# FeedbackLoop.net
KiCad netlist of a schematic drawn in Altium Designer
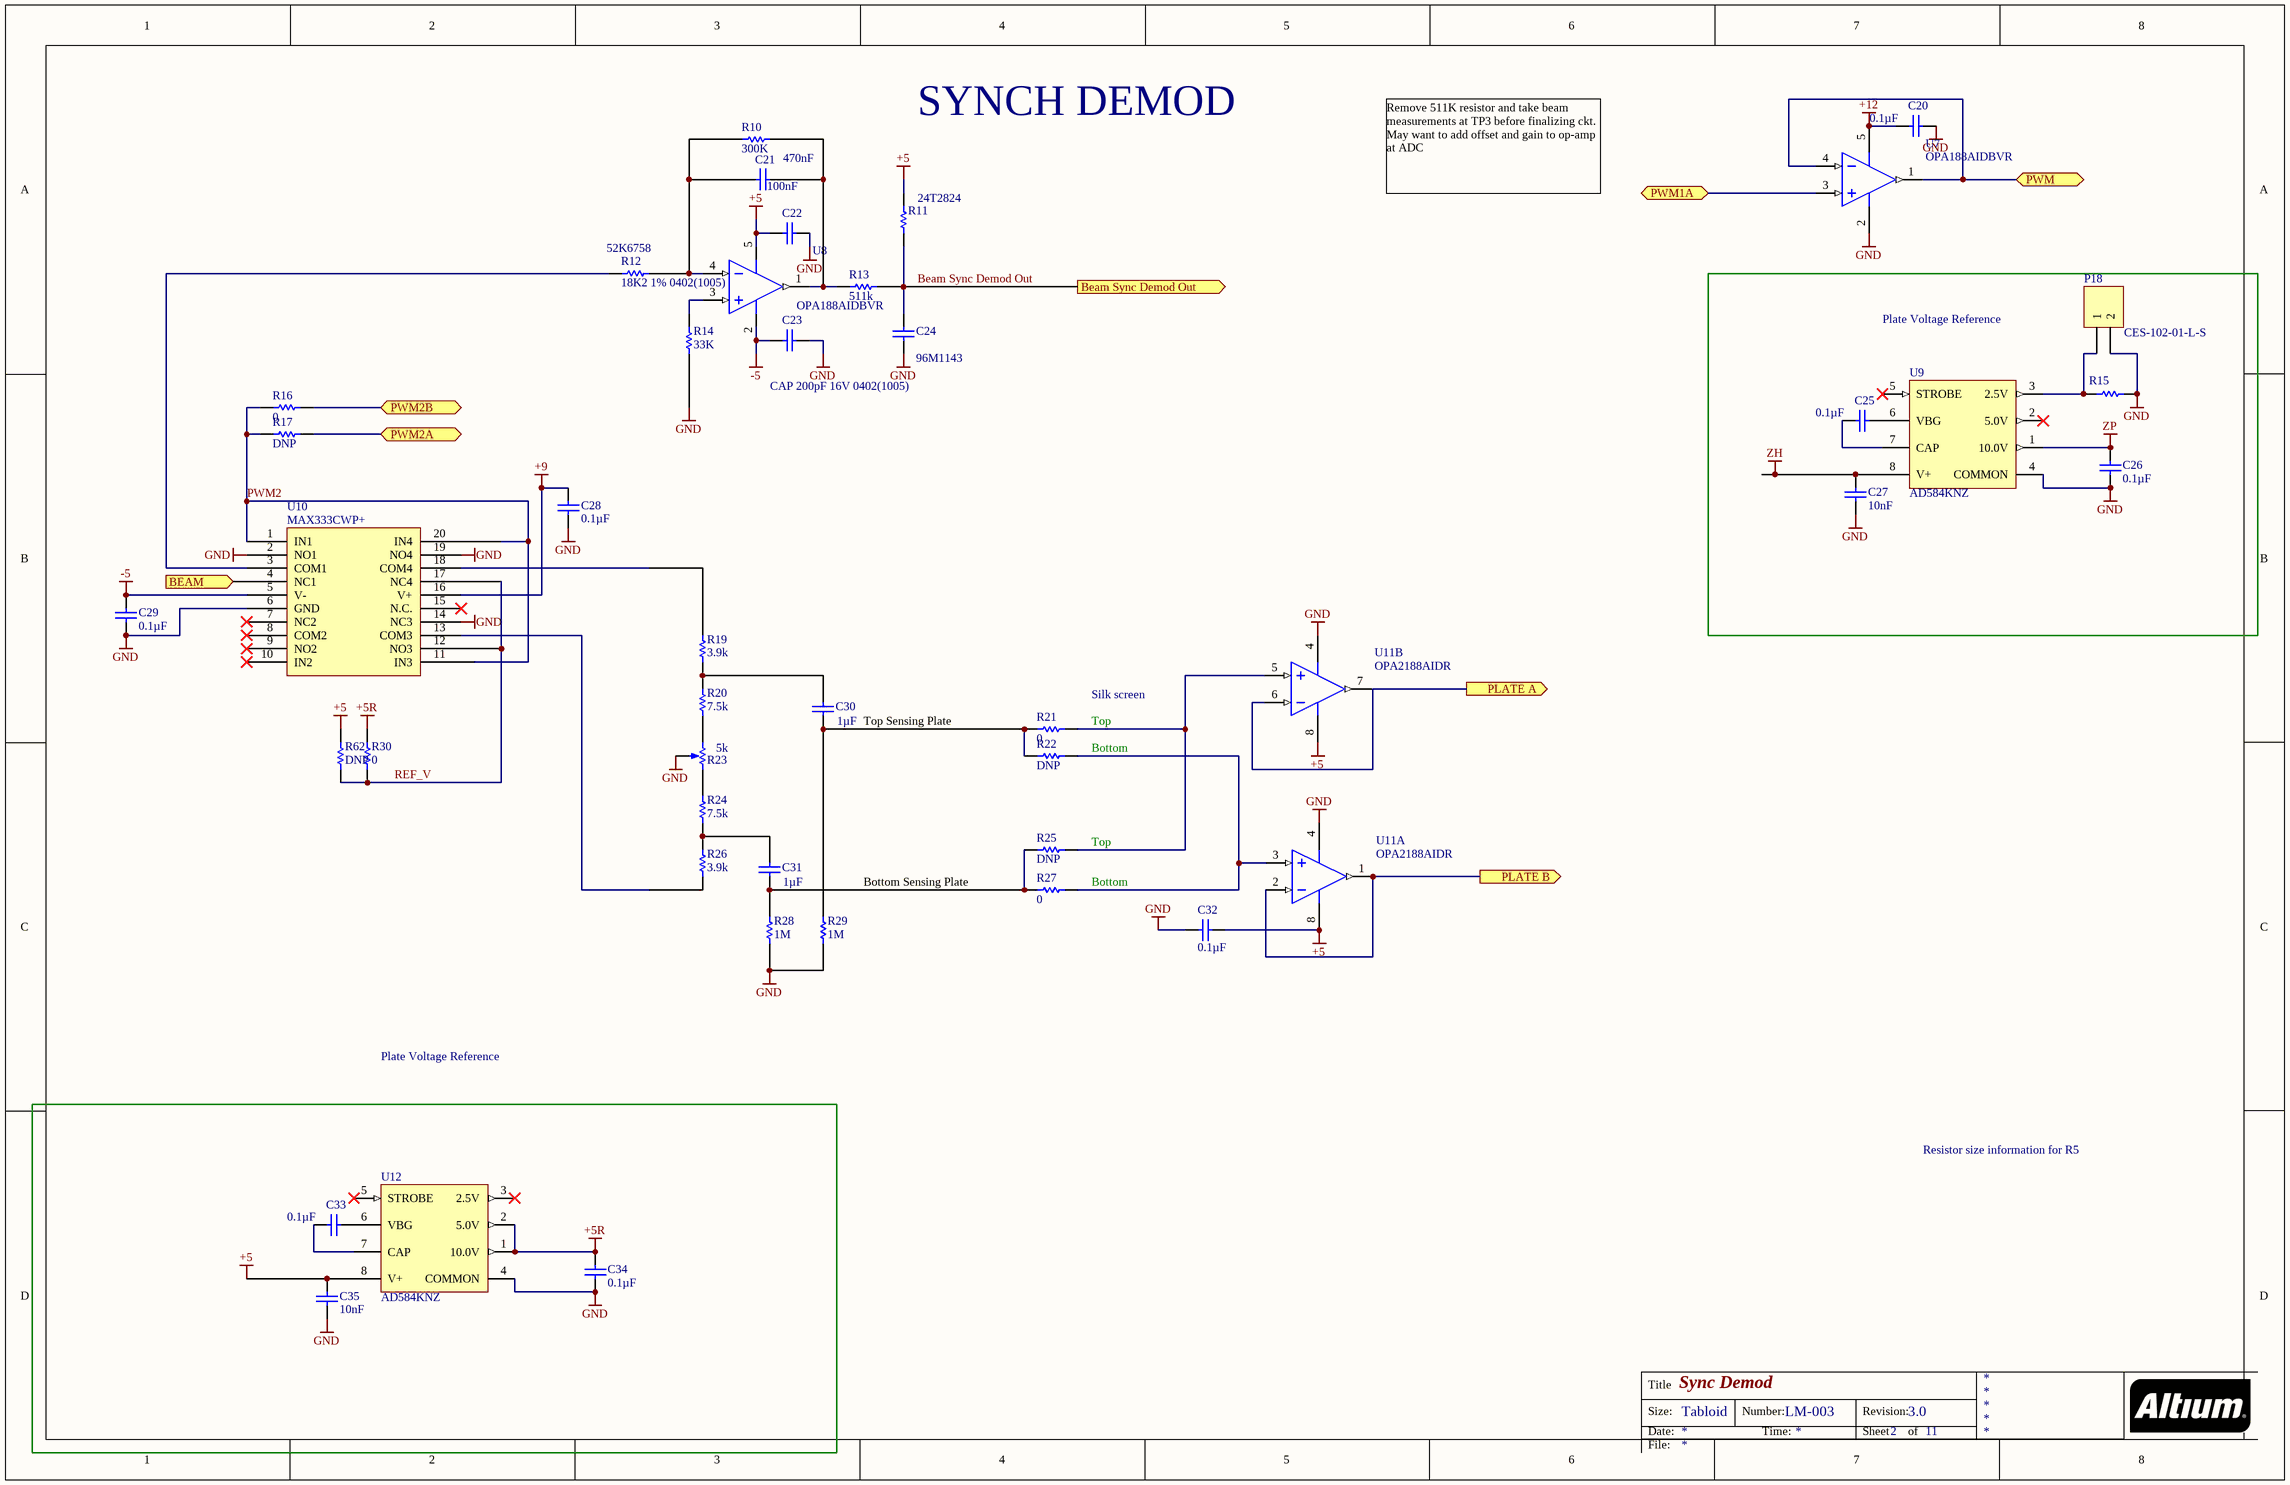
[diagram p0: FeedbackLoop.SchDoc]

(export (version "E")
  (design (tool "Eeschema 10.0.6"))
  (components
    (comp (ref "C20")
      (value "CAP 100nF 25V 0805(2012)")
      (footprint "CAPC0805(2012)100_N")
      (description "CAP 100nF 25V -20% to +80% 0805 (2012 Metric) Thickness 1mm SMD")
      (fields
        (field (name "MANUFACTURER") "Murata Electronics North America")
        (field (name "MANUFACTURER PART NUMBER") "GRM21BR71E104KA01L")
        (field (name "CAPACITANCE") "0.1µF")
      )
      (libsource (lib "Altium Content Vault") (part "CMP-1036-04416-1"))
    )
    (comp (ref "C21")
      (value "~")
      (footprint "CAPC0402(1005)60_L")
      (fields
        (field (name "MANUFACTURER") "TDK")
        (field (name "MANUFACTURER PART NUMBER") "C1005X5R1E474M050BB")
        (field (name "TOLERANCE") "20%")
        (field (name "CAPACITANCE") "470nF")
      )
      (libsource (lib "Altium Content Vault") (part "CMP-1034-01343-1"))
    )
    (comp (ref "C22")
      (value "~")
      (footprint "CAPC0402(1005)60_L")
      (fields
        (field (name "MANUFACTURER") "Kemet")
        (field (name "MANUFACTURER PART NUMBER") "C0402C104K4RACAUTO")
        (field (name "CAPACITANCE") "100nF")
        (field (name "TOLERANCE") "10%")
      )
      (libsource (lib "Altium Content Vault") (part "CMP-1034-01343-1"))
    )
    (comp (ref "C23")
      (value "CAP 200pF 16V 0402(1005)")
      (footprint "CAPC0402(1005)60_L")
      (description "CAP 200pF 16V ±2% 0402 (1005 Metric) Thickness 0.6mm SMD")
      (fields (field (name "TOLERANCE") "Â±2%") (field (name "MANUFACTURER") "Kemet"))
      (libsource (lib "Altium Content Vault") (part "CMP-1034-01343-1"))
    )
    (comp (ref "C24")
      (value "~")
      (footprint "CAPC0402(1005)60_L")
      (fields
        (field (name "SUPPLIER PART NUMBER 1") "96M1143")
        (field (name "MANUFACTURER") "AVX")
        (field (name "MANUFACTURER PART NUMBER") "04025A220JAT2A")
      )
      (libsource (lib "Altium Content Vault") (part "CMP-1034-01343-1"))
    )
    (comp (ref "C25")
      (value "CAP 100nF 25V 0805(2012)")
      (footprint "CAPC0805(2012)100_N")
      (description "CAP 100nF 25V -20% to +80% 0805 (2012 Metric) Thickness 1mm SMD")
      (fields
        (field (name "MANUFACTURER") "Murata Electronics North America")
        (field (name "MANUFACTURER PART NUMBER") "GRM21BR71E104KA01L")
        (field (name "CAPACITANCE") "0.1µF")
      )
      (libsource (lib "Altium Content Vault") (part "CMP-1036-04416-1"))
    )
    (comp (ref "C26")
      (value "CAP CER 0.1UF 25V X7R 0805")
      (footprint "CAPC0805(2012)145_N")
      (fields
        (field (name "MANUFACTURER") "Murata Electronics North America")
        (field (name "MANUFACTURER PART NUMBER") "GRM21BR71E104KA01L")
        (field (name "CAPACITANCE") "0.1µF")
        (field (name "TOLERANCE") "±10%")
      )
      (libsource (lib "Altium Content Vault") (part "CMP-1036-04795-1"))
    )
    (comp (ref "C27")
      (value "Multilayer Ceramic Capacitors MLCC - SMD/SMT 0.01uF 50volts 10% X7R")
      (footprint "CAPC0805(2012)145_N")
      (fields
        (field (name "MANUFACTURER") "Kemet")
        (field (name "MANUFACTURER PART NUMBER") "C0805C103K5RACAUTO")
        (field (name "CAPACITANCE") "10nF")
        (field (name "TOLERANCE") "10%")
      )
      (libsource (lib "Altium Content Vault") (part "CMP-1036-04795-1"))
    )
    (comp (ref "C28")
      (value "CAP CER 0.1UF 25V X7R 0805")
      (footprint "CAPC0805(2012)145_N")
      (fields
        (field (name "MANUFACTURER") "Murata Electronics North America")
        (field (name "MANUFACTURER PART NUMBER") "GRM21BR71E104KA01L")
        (field (name "CAPACITANCE") "0.1µF")
        (field (name "TOLERANCE") "±10%")
      )
      (libsource (lib "Altium Content Vault") (part "CMP-1036-04795-1"))
    )
    (comp (ref "C29")
      (value "CAP CER 0.1UF 25V X7R 0805")
      (footprint "CAPC0805(2012)145_N")
      (fields
        (field (name "MANUFACTURER") "Murata Electronics North America")
        (field (name "MANUFACTURER PART NUMBER") "GRM21BR71E104KA01L")
        (field (name "CAPACITANCE") "0.1µF")
        (field (name "TOLERANCE") "±10%")
      )
      (libsource (lib "Altium Content Vault") (part "CMP-1036-04795-1"))
    )
    (comp (ref "C30")
      (value "CAP CER 1UF 25V X7R 0805")
      (footprint "CAPC0805(2012)155_L")
      (fields
        (field (name "MANUFACTURER") "Murata Electronics North America")
        (field (name "MANUFACTURER PART NUMBER") "GRM21BR71E105KA99L")
        (field (name "CAPACITANCE") "1µF")
        (field (name "TOLERANCE") "±10%")
      )
      (libsource (lib "Altium Content Vault") (part "CMP-1036-04882-1"))
    )
    (comp (ref "C31")
      (value "CAP CER 1UF 25V X7R 0805")
      (footprint "CAPC0805(2012)155_L")
      (fields
        (field (name "MANUFACTURER") "Murata Electronics North America")
        (field (name "MANUFACTURER PART NUMBER") "GRM21BR71E105KA99L")
        (field (name "CAPACITANCE") "1µF")
        (field (name "TOLERANCE") "±10%")
      )
      (libsource (lib "Altium Content Vault") (part "CMP-1036-04882-1"))
    )
    (comp (ref "C32")
      (value "CAP CER 0.1UF 25V X7R 0805")
      (footprint "CAPC0805(2012)155_L")
      (fields
        (field (name "MANUFACTURER") "Murata Electronics North America")
        (field (name "MANUFACTURER PART NUMBER") "GRM21BR71E104KA01L")
        (field (name "CAPACITANCE") "0.1µF")
        (field (name "TOLERANCE") "±10%")
      )
      (libsource (lib "Altium Content Vault") (part "CMP-1036-04882-1"))
    )
    (comp (ref "C33")
      (value "CAP 100nF 25V 0805(2012)")
      (footprint "CAPC0805(2012)100_N")
      (description "CAP 100nF 25V -20% to +80% 0805 (2012 Metric) Thickness 1mm SMD")
      (fields
        (field (name "MANUFACTURER") "Murata Electronics North America")
        (field (name "MANUFACTURER PART NUMBER") "GRM21BR71E104KA01L")
        (field (name "CAPACITANCE") "0.1µF")
      )
      (libsource (lib "Altium Content Vault") (part "CMP-1036-04416-1"))
    )
    (comp (ref "C34")
      (value "CAP CER 0.1UF 25V X7R 0805")
      (footprint "CAPC0805(2012)145_N")
      (fields
        (field (name "MANUFACTURER") "Murata Electronics North America")
        (field (name "MANUFACTURER PART NUMBER") "GRM21BR71E104KA01L")
        (field (name "CAPACITANCE") "0.1µF")
        (field (name "TOLERANCE") "±10%")
      )
      (libsource (lib "Altium Content Vault") (part "CMP-1036-04795-1"))
    )
    (comp (ref "C35")
      (value "Multilayer Ceramic Capacitors MLCC - SMD/SMT 0.01uF 50volts 10% X7R")
      (footprint "CAPC0805(2012)145_N")
      (fields
        (field (name "MANUFACTURER") "Kemet")
        (field (name "MANUFACTURER PART NUMBER") "C0805C103K5RACAUTO")
        (field (name "CAPACITANCE") "10nF")
        (field (name "TOLERANCE") "10%")
      )
      (libsource (lib "Altium Content Vault") (part "CMP-1036-04795-1"))
    )
    (comp (ref "P18")
      (value "LOW PROFILE .025\" SQUARE STRIPS")
      (footprint "CES-102-01-L-S")
      (fields
        (field (name "MANUFACTURER") "Samtec Inc.")
        (field (name "MANUFACTURER PART NUMBER") "CES-102-01-L-S")
      )
      (libsource (lib "Miscellaneous Connectors") (part "Header 2"))
    )
    (comp (ref "R10")
      (value "300K")
      (footprint "RESC0402(1005)_M")
      (libsource (lib "Altium Content Vault") (part "CMP-1011-00651-1"))
    )
    (comp (ref "R11")
      (value "~")
      (footprint "RESC0402(1005)_M")
      (fields
        (field (name "SUPPLIER PART NUMBER 1") "24T2824")
        (field (name "MANUFACTURER") "VISHAY")
        (field (name "MANUFACTURER PART NUMBER") "CRCW0402100KFKEDHP")
      )
      (libsource (lib "Altium Content Vault") (part "CMP-1011-00651-1"))
    )
    (comp (ref "R12")
      (value "18K2 1% 0402(1005)")
      (footprint "RESC0402(1005)_M")
      (description "18K2 0.063W 1% 0402 (1005 Metric)  SMD")
      (fields
        (field (name "SUPPLIER PART NUMBER 1") "52K6758")
        (field (name "MANUFACTURER") "VISHAY")
        (field (name "MANUFACTURER PART NUMBER") "CRCW040218K2FKED")
      )
      (libsource (lib "Altium Content Vault") (part "CMP-1011-00651-1"))
    )
    (comp (ref "R13")
      (value "511k")
      (footprint "RESC0402(1005)_M")
      (libsource (lib "Altium Content Vault") (part "CMP-1011-00651-1"))
    )
    (comp (ref "R14")
      (value "33K")
      (footprint "RESC0402(1005)_M")
      (libsource (lib "Altium Content Vault") (part "CMP-1011-00651-1"))
    )
    (comp (ref "R15")
      (value "TBD")
      (footprint "VH102K")
      (libsource (lib "altium-import") (part "root_0_CMP-1013-00393-1_"))
    )
    (comp (ref "R16")
      (value "0")
      (footprint "RESC0402(1005)_M")
      (libsource (lib "Altium Content Vault") (part "CMP-1011-00651-1"))
    )
    (comp (ref "R17")
      (value "DNP")
      (footprint "RESC0402(1005)_M")
      (libsource (lib "Altium Content Vault") (part "CMP-1011-00651-1"))
    )
    (comp (ref "R19")
      (value "3.9k")
      (footprint "RESC0402(1005)_M")
      (libsource (lib "Altium Content Vault") (part "CMP-1011-00651-1"))
    )
    (comp (ref "R20")
      (value "7.5k")
      (footprint "RESC0402(1005)_M")
      (libsource (lib "Altium Content Vault") (part "CMP-1011-00651-1"))
    )
    (comp (ref "R21")
      (value "0")
      (footprint "RESC0402(1005)_M")
      (libsource (lib "Altium Content Vault") (part "CMP-1011-00651-1"))
    )
    (comp (ref "R22")
      (value "DNP")
      (footprint "RESC0402(1005)_M")
      (libsource (lib "Altium Content Vault") (part "CMP-1011-00651-1"))
    )
    (comp (ref "R23")
      (value "TRIMMER 5K OHM 0.25W PC PIN")
      (footprint "Trimmer 2.54")
      (fields
        (field (name "MANUFACTURER") "Vishay Foil Resistors (Division of Vishay Precision Group)")
        (field (name "MANUFACTURER PART NUMBER") "Y00535K00000J0L")
        (field (name "RESISTANCE (OHMS)") "5k")
        (field (name "TOLERANCE") "±5%")
      )
      (libsource (lib "ZLS_Schematic_lib") (part "Trimmer"))
    )
    (comp (ref "R24")
      (value "7.5k")
      (footprint "RESC0402(1005)_M")
      (libsource (lib "Altium Content Vault") (part "CMP-1011-00651-1"))
    )
    (comp (ref "R25")
      (value "DNP")
      (footprint "RESC0402(1005)_M")
      (libsource (lib "Altium Content Vault") (part "CMP-1011-00651-1"))
    )
    (comp (ref "R26")
      (value "3.9k")
      (footprint "RESC0402(1005)_M")
      (libsource (lib "Altium Content Vault") (part "CMP-1011-00651-1"))
    )
    (comp (ref "R27")
      (value "0")
      (footprint "RESC0402(1005)_M")
      (libsource (lib "Altium Content Vault") (part "CMP-1011-00651-1"))
    )
    (comp (ref "R28")
      (value "1M")
      (footprint "RESC0402(1005)_M")
      (libsource (lib "Altium Content Vault") (part "CMP-1011-00651-1"))
    )
    (comp (ref "R29")
      (value "1M")
      (footprint "RESC0402(1005)_M")
      (libsource (lib "Altium Content Vault") (part "CMP-1011-00651-1"))
    )
    (comp (ref "R30")
      (value "0")
      (footprint "RESC0402(1005)_M")
      (libsource (lib "Altium Content Vault") (part "CMP-1011-00651-1"))
    )
    (comp (ref "R62")
      (value "DNP")
      (footprint "RESC0402(1005)_M")
      (libsource (lib "Altium Content Vault") (part "CMP-1011-00651-1"))
    )
    (comp (ref "U7")
      (value "OPA188AIDBVR")
      (footprint "DBV0005A_M")
      (fields (field (name "MANUFACTURER") "Texas Instruments"))
      (libsource (lib "Altium Content Vault") (part "CMP-0809-00005-2"))
    )
    (comp (ref "U8")
      (value "OPA188AIDBVR")
      (footprint "DBV0005A_M")
      (fields (field (name "MANUFACTURER") "Texas Instruments"))
      (libsource (lib "Altium Content Vault") (part "CMP-0809-00005-2"))
    )
    (comp (ref "U9")
      (value "AD584KNZ")
      (footprint "ADI-N-8")
      (fields (field (name "MANUFACTURER") "Analog Devices"))
      (libsource (lib "Altium Content Vault") (part "ADI-AD584-N-8"))
    )
    (comp (ref "U10")
      (value "MAX333CWP+")
      (footprint "TSOP65P640X90-20N")
      (description "IC SWITCH QUAD SPDT 20TSSOP")
      (fields (field (name "MANUFACTURER") "Maxim") (field (name "MANUFACTURER PART NUMBER") "MAX333AEUP+"))
      (libsource (lib "ZLS_Schematic_lib") (part "MAX333CWP+"))
    )
    (comp (ref "U11")
      (value "OPA2188AIDR")
      (footprint "D0008A_L")
      (fields (field (name "MANUFACTURER") "Texas Instruments"))
      (libsource (lib "Altium Content Vault") (part "CMP-0272-00241-3"))
    )
    (comp (ref "U12")
      (value "AD584KNZ")
      (footprint "ADI-N-8")
      (fields (field (name "MANUFACTURER") "Analog Devices"))
      (libsource (lib "Altium Content Vault") (part "ADI-AD584-N-8"))
    )
  )
  (nets
    (net (code "1") (name "+5") (class "Default")
      (node (ref "C22") (pin "1") (pinfunction "1_1") (pintype "passive"))
      (node (ref "C32") (pin "1") (pinfunction "1_1") (pintype "passive"))
      (node (ref "C35") (pin "1") (pinfunction "1_1") (pintype "passive"))
      (node (ref "R11") (pin "2") (pinfunction "2_2") (pintype "passive"))
      (node (ref "R62") (pin "2") (pinfunction "2_2") (pintype "passive"))
      (node (ref "U11") (pin "8") (pinfunction "V+_8") (pintype "power_in"))
      (node (ref "U12") (pin "8") (pinfunction "V+_8") (pintype "power_in"))
      (node (ref "U8") (pin "5") (pinfunction "V+_5") (pintype "power_in"))
    )
    (net (code "2") (name "+5R") (class "Default")
      (node (ref "C34") (pin "1") (pinfunction "1_1") (pintype "passive"))
      (node (ref "R30") (pin "2") (pinfunction "2_2") (pintype "passive"))
      (node (ref "U12") (pin "1") (pinfunction "10.0V_1") (pintype "output"))
      (node (ref "U12") (pin "2") (pinfunction "5.0V_2") (pintype "output"))
    )
    (net (code "3") (name "+9") (class "Default")
      (node (ref "C28") (pin "2") (pinfunction "2_2") (pintype "passive"))
      (node (ref "U10") (pin "16") (pinfunction "V+_16") (pintype "power_in"))
    )
    (net (code "4") (name "+12") (class "Default")
      (node (ref "C20") (pin "1") (pinfunction "1_1") (pintype "passive"))
      (node (ref "U7") (pin "5") (pinfunction "V+_5") (pintype "power_in"))
    )
    (net (code "5") (name "-5") (class "Default")
      (node (ref "C23") (pin "1") (pinfunction "1_1") (pintype "passive"))
      (node (ref "C29") (pin "1") (pinfunction "1_1") (pintype "passive"))
      (node (ref "U10") (pin "5") (pinfunction "V-_5") (pintype "power_in"))
      (node (ref "U8") (pin "2") (pinfunction "V-_2") (pintype "power_in"))
    )
    (net (code "6") (name "/BEAM") (class "Default")
      (node (ref "U10") (pin "4") (pinfunction "NC1_4") (pintype "passive"))
    )
    (net (code "7") (name "/Beam Sync Demod Out") (class "Default")
      (node (ref "C24") (pin "2") (pinfunction "2_2") (pintype "passive"))
      (node (ref "R11") (pin "1") (pinfunction "1_1") (pintype "passive"))
      (node (ref "R13") (pin "2") (pinfunction "2_2") (pintype "passive"))
    )
    (net (code "8") (name "/PLATE A") (class "Default")
      (node (ref "U11") (pin "6") (pinfunction "IN_B-_6") (pintype "input"))
    )
    (net (code "9") (name "/PLATE B") (class "Default")
      (node (ref "U11") (pin "1") (pinfunction "OUT_A_1") (pintype "output"))
      (node (ref "U11") (pin "2") (pinfunction "IN_A-_2") (pintype "input"))
    )
    (net (code "10") (name "/PWM") (class "Default")
      (node (ref "U7") (pin "1") (pinfunction "OUT_1") (pintype "output"))
      (node (ref "U7") (pin "4") (pinfunction "IN-_4") (pintype "input"))
    )
    (net (code "11") (name "/PWM1A") (class "Default")
      (node (ref "U7") (pin "3") (pinfunction "IN+_3") (pintype "input"))
    )
    (net (code "12") (name "/PWM2") (class "Default")
      (node (ref "R16") (pin "2") (pinfunction "2_2") (pintype "passive"))
      (node (ref "R17") (pin "2") (pinfunction "2_2") (pintype "passive"))
      (node (ref "U10") (pin "1") (pinfunction "IN1_1") (pintype "passive"))
      (node (ref "U10") (pin "11") (pinfunction "IN3_11") (pintype "passive"))
      (node (ref "U10") (pin "20") (pinfunction "IN4_20") (pintype "passive"))
    )
    (net (code "13") (name "/PWM2A") (class "Default")
      (node (ref "R17") (pin "1") (pinfunction "1_1") (pintype "passive"))
    )
    (net (code "14") (name "/PWM2B") (class "Default")
      (node (ref "R16") (pin "1") (pinfunction "1_1") (pintype "passive"))
    )
    (net (code "15") (name "/REF_V") (class "Default")
      (node (ref "R30") (pin "1") (pinfunction "1_1") (pintype "passive"))
      (node (ref "R62") (pin "1") (pinfunction "1_1") (pintype "passive"))
      (node (ref "U10") (pin "12") (pinfunction "NO3_12") (pintype "passive"))
      (node (ref "U10") (pin "17") (pinfunction "NC4_17") (pintype "passive"))
    )
    (net (code "16") (name "GND") (class "Default")
      (node (ref "C20") (pin "2") (pinfunction "2_2") (pintype "passive"))
      (node (ref "C22") (pin "2") (pinfunction "2_2") (pintype "passive"))
      (node (ref "C23") (pin "2") (pinfunction "2_2") (pintype "passive"))
      (node (ref "C24") (pin "1") (pinfunction "1_1") (pintype "passive"))
      (node (ref "C26") (pin "2") (pinfunction "2_2") (pintype "passive"))
      (node (ref "C27") (pin "2") (pinfunction "2_2") (pintype "passive"))
      (node (ref "C28") (pin "1") (pinfunction "1_1") (pintype "passive"))
      (node (ref "C29") (pin "2") (pinfunction "2_2") (pintype "passive"))
      (node (ref "C32") (pin "2") (pinfunction "2_2") (pintype "passive"))
      (node (ref "C34") (pin "2") (pinfunction "2_2") (pintype "passive"))
      (node (ref "C35") (pin "2") (pinfunction "2_2") (pintype "passive"))
      (node (ref "P18") (pin "2") (pinfunction "2_2") (pintype "passive"))
      (node (ref "R14") (pin "1") (pinfunction "1_1") (pintype "passive"))
      (node (ref "R15") (pin "2") (pinfunction "2_2") (pintype "passive"))
      (node (ref "R23") (pin "2") (pinfunction "b_2") (pintype "passive"))
      (node (ref "R28") (pin "1") (pinfunction "1_1") (pintype "passive"))
      (node (ref "R29") (pin "1") (pinfunction "1_1") (pintype "passive"))
      (node (ref "U10") (pin "14") (pinfunction "NC3_14") (pintype "passive"))
      (node (ref "U10") (pin "19") (pinfunction "NO4_19") (pintype "passive"))
      (node (ref "U10") (pin "2") (pinfunction "NO1_2") (pintype "passive"))
      (node (ref "U10") (pin "6") (pinfunction "GND_6") (pintype "passive"))
      (node (ref "U11") (pin "4") (pinfunction "V-_4") (pintype "power_in"))
      (node (ref "U12") (pin "4") (pinfunction "COMMON_4") (pintype "passive"))
      (node (ref "U7") (pin "2") (pinfunction "V-_2") (pintype "power_in"))
      (node (ref "U9") (pin "4") (pinfunction "COMMON_4") (pintype "passive"))
    )
    (net (code "17") (name "Net-(C30-Pad1)") (class "Default")
      (node (ref "C30") (pin "1") (pinfunction "1_1") (pintype "passive"))
      (node (ref "R21") (pin "2") (pinfunction "2_2") (pintype "passive"))
      (node (ref "R22") (pin "2") (pinfunction "2_2") (pintype "passive"))
      (node (ref "R29") (pin "2") (pinfunction "2_2") (pintype "passive"))
    )
    (net (code "18") (name "Net-(C30-Pad2)") (class "Default")
      (node (ref "C30") (pin "2") (pinfunction "2_2") (pintype "passive"))
      (node (ref "R19") (pin "1") (pinfunction "1_1") (pintype "passive"))
      (node (ref "R20") (pin "2") (pinfunction "2_2") (pintype "passive"))
    )
    (net (code "19") (name "Net-(C31-Pad1)") (class "Default")
      (node (ref "C31") (pin "1") (pinfunction "1_1") (pintype "passive"))
      (node (ref "R25") (pin "2") (pinfunction "2_2") (pintype "passive"))
      (node (ref "R27") (pin "2") (pinfunction "2_2") (pintype "passive"))
      (node (ref "R28") (pin "2") (pinfunction "2_2") (pintype "passive"))
    )
    (net (code "20") (name "Net-(C31-Pad2)") (class "Default")
      (node (ref "C31") (pin "2") (pinfunction "2_2") (pintype "passive"))
      (node (ref "R24") (pin "1") (pinfunction "1_1") (pintype "passive"))
      (node (ref "R26") (pin "2") (pinfunction "2_2") (pintype "passive"))
    )
    (net (code "21") (name "Net-(R23-a)") (class "Default")
      (node (ref "R23") (pin "1") (pinfunction "a_1") (pintype "passive"))
      (node (ref "R24") (pin "2") (pinfunction "2_2") (pintype "passive"))
    )
    (net (code "22") (name "Net-(R23-c)") (class "Default")
      (node (ref "R20") (pin "1") (pinfunction "1_1") (pintype "passive"))
      (node (ref "R23") (pin "3") (pinfunction "c_3") (pintype "passive"))
    )
    (net (code "23") (name "Net-(U8-IN+)") (class "Default")
      (node (ref "R14") (pin "2") (pinfunction "2_2") (pintype "passive"))
      (node (ref "U8") (pin "3") (pinfunction "IN+_3") (pintype "input"))
    )
    (net (code "24") (name "Net-(U8-IN-)") (class "Default")
      (node (ref "C21") (pin "1") (pinfunction "1_1") (pintype "passive"))
      (node (ref "R10") (pin "1") (pinfunction "1_1") (pintype "passive"))
      (node (ref "R12") (pin "2") (pinfunction "2_2") (pintype "passive"))
      (node (ref "U8") (pin "4") (pinfunction "IN-_4") (pintype "input"))
    )
    (net (code "25") (name "Net-(U8-OUT)") (class "Default")
      (node (ref "C21") (pin "2") (pinfunction "2_2") (pintype "passive"))
      (node (ref "R10") (pin "2") (pinfunction "2_2") (pintype "passive"))
      (node (ref "R13") (pin "1") (pinfunction "1_1") (pintype "passive"))
      (node (ref "U8") (pin "1") (pinfunction "OUT_1") (pintype "output"))
    )
    (net (code "26") (name "Net-(U9-2.5V)") (class "Default")
      (node (ref "P18") (pin "1") (pinfunction "1_1") (pintype "passive"))
      (node (ref "R15") (pin "1") (pinfunction "1_1") (pintype "passive"))
      (node (ref "U9") (pin "3") (pinfunction "2.5V_3") (pintype "output"))
    )
    (net (code "27") (name "Net-(U9-CAP)") (class "Default")
      (node (ref "C25") (pin "1") (pinfunction "1_1") (pintype "passive"))
      (node (ref "U9") (pin "7") (pinfunction "CAP_7") (pintype "passive"))
    )
    (net (code "28") (name "Net-(U9-VBG)") (class "Default")
      (node (ref "C25") (pin "2") (pinfunction "2_2") (pintype "passive"))
      (node (ref "U9") (pin "6") (pinfunction "VBG_6") (pintype "passive"))
    )
    (net (code "29") (name "Net-(U10-COM1)") (class "Default")
      (node (ref "R12") (pin "1") (pinfunction "1_1") (pintype "passive"))
      (node (ref "U10") (pin "3") (pinfunction "COM1_3") (pintype "passive"))
    )
    (net (code "30") (name "Net-(U10-COM3)") (class "Default")
      (node (ref "R26") (pin "1") (pinfunction "1_1") (pintype "passive"))
      (node (ref "U10") (pin "13") (pinfunction "COM3_13") (pintype "passive"))
    )
    (net (code "31") (name "Net-(U10-COM4)") (class "Default")
      (node (ref "R19") (pin "2") (pinfunction "2_2") (pintype "passive"))
      (node (ref "U10") (pin "18") (pinfunction "COM4_18") (pintype "passive"))
    )
    (net (code "32") (name "Net-(U11A-IN_A+)") (class "Default")
      (node (ref "R22") (pin "1") (pinfunction "1_1") (pintype "passive"))
      (node (ref "R27") (pin "1") (pinfunction "1_1") (pintype "passive"))
      (node (ref "U11") (pin "3") (pinfunction "IN_A+_3") (pintype "input"))
    )
    (net (code "33") (name "Net-(U11B-IN_B+)") (class "Default")
      (node (ref "R21") (pin "1") (pinfunction "1_1") (pintype "passive"))
      (node (ref "R25") (pin "1") (pinfunction "1_1") (pintype "passive"))
      (node (ref "U11") (pin "5") (pinfunction "IN_B+_5") (pintype "input"))
    )
    (net (code "34") (name "Net-(U12-CAP)") (class "Default")
      (node (ref "C33") (pin "1") (pinfunction "1_1") (pintype "passive"))
      (node (ref "U12") (pin "7") (pinfunction "CAP_7") (pintype "passive"))
    )
    (net (code "35") (name "Net-(U12-VBG)") (class "Default")
      (node (ref "C33") (pin "2") (pinfunction "2_2") (pintype "passive"))
      (node (ref "U12") (pin "6") (pinfunction "VBG_6") (pintype "passive"))
    )
    (net (code "36") (name "ZH") (class "Default")
      (node (ref "C27") (pin "1") (pinfunction "1_1") (pintype "passive"))
      (node (ref "U9") (pin "8") (pinfunction "V+_8") (pintype "power_in"))
    )
    (net (code "37") (name "ZP") (class "Default")
      (node (ref "C26") (pin "1") (pinfunction "1_1") (pintype "passive"))
      (node (ref "U9") (pin "1") (pinfunction "10.0V_1") (pintype "output"))
    )
    (net (code "38") (name "unconnected-(U9-5.0V-Pad2)") (class "Default")
      (node (ref "U9") (pin "2") (pinfunction "5.0V_2") (pintype "output+no_connect"))
    )
    (net (code "39") (name "unconnected-(U9-STROBE-Pad5)") (class "Default")
      (node (ref "U9") (pin "5") (pinfunction "STROBE_5") (pintype "input+no_connect"))
    )
    (net (code "40") (name "unconnected-(U10-COM2-Pad8)") (class "Default")
      (node (ref "U10") (pin "8") (pinfunction "COM2_8") (pintype "passive+no_connect"))
    )
    (net (code "41") (name "unconnected-(U10-IN2-Pad10)") (class "Default")
      (node (ref "U10") (pin "10") (pinfunction "IN2_10") (pintype "passive+no_connect"))
    )
    (net (code "42") (name "unconnected-(U10-N.C.-Pad15)") (class "Default")
      (node (ref "U10") (pin "15") (pinfunction "N.C._15") (pintype "passive+no_connect"))
    )
    (net (code "43") (name "unconnected-(U10-NC2-Pad7)") (class "Default")
      (node (ref "U10") (pin "7") (pinfunction "NC2_7") (pintype "passive+no_connect"))
    )
    (net (code "44") (name "unconnected-(U10-NO2-Pad9)") (class "Default")
      (node (ref "U10") (pin "9") (pinfunction "NO2_9") (pintype "passive+no_connect"))
    )
    (net (code "45") (name "unconnected-(U11B-OUT_B-Pad7)") (class "Default")
      (node (ref "U11") (pin "7") (pinfunction "OUT_B_7") (pintype "output"))
    )
    (net (code "46") (name "unconnected-(U12-2.5V-Pad3)") (class "Default")
      (node (ref "U12") (pin "3") (pinfunction "2.5V_3") (pintype "output+no_connect"))
    )
    (net (code "47") (name "unconnected-(U12-STROBE-Pad5)") (class "Default")
      (node (ref "U12") (pin "5") (pinfunction "STROBE_5") (pintype "input+no_connect"))
    )
  )
)
